# FLASH.net
KiCad netlist of a schematic drawn in Altium Designer
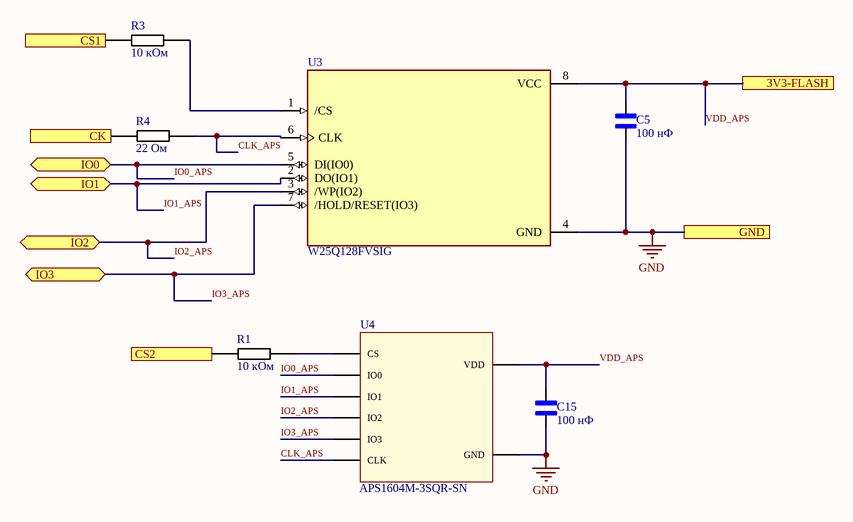
[diagram p0: FLASH.SchDoc]

(export (version "E")
  (design (tool "Eeschema 10.0.6"))
  (components
    (comp (ref "C5")
      (value "100 нФ")
      (footprint "CAPC1005X22N")
      (description "SMD Capacitor X5R(EIA) with Capacitance: 0.10uF Tol. 10%. Rated Voltage: 6.3Vdc")
      (fields (field (name "MF") "Murata") (field (name "MP") "GRM152R60J104KE19D"))
      (libsource (lib "GRM152R60J104KE19D") (part "GRM152R60J104KE19D"))
    )
    (comp (ref "C15")
      (value "100 нФ")
      (footprint "CAPC1005X22N")
      (description "SMD Capacitor X5R(EIA) with Capacitance: 0.10uF Tol. 10%. Rated Voltage: 6.3Vdc")
      (fields (field (name "MF") "Murata") (field (name "MP") "GRM152R60J104KE19D"))
      (libsource (lib "GRM152R60J104KE19D") (part "GRM152R60J104KE19D"))
    )
    (comp (ref "R1")
      (value "10 кОм")
      (footprint "Yageo RC0805JR-0710KL")
      (libsource (lib "Schlib1") (part "Yageo RC0805JR-0710KL"))
    )
    (comp (ref "R3")
      (value "10 кОм")
      (footprint "Yageo RC0805JR-0710KL")
      (libsource (lib "Schlib1") (part "Yageo RC0805JR-0710KL"))
    )
    (comp (ref "R4")
      (value "22 Ом")
      (footprint "CR0805-JW-220ELF")
      (libsource (lib "Schlib1") (part "CR0805-JW-220ELF"))
    )
    (comp (ref "U3")
      (value "W25Q128FVSIG")
      (footprint "SOIC127P790X216-8N")
      (description "FLASH - NOR Memory IC 128Mb (16M x 8) SPI - Quad I/O, QPI, DTR 133 MHz 8-SOIC")
      (fields (field (name "MF") "Winbond Electronics") (field (name "MP") "W25Q128JVSIQ"))
      (libsource (lib "W25Q128JVSIQ") (part "W25Q128JVSIQ"))
    )
    (comp (ref "U4")
      (value "APS1604M-3SQR-SN")
      (footprint "APS1604M (SOP-8)")
      (libsource (lib "Schlib1") (part "APS1604M"))
    )
  )
  (nets
    (net (code "1") (name "/CK") (class "Default")
      (node (ref "R4") (pin "1") (pinfunction "7_1") (pintype "passive"))
    )
    (net (code "2") (name "/CLK_APS") (class "Default")
      (node (ref "R4") (pin "2") (pinfunction "2_2") (pintype "passive"))
      (node (ref "U3") (pin "6") (pinfunction "CLK_6") (pintype "input"))
      (node (ref "U4") (pin "6") (pinfunction "CLK_6") (pintype "passive"))
    )
    (net (code "3") (name "/CS1") (class "Default")
      (node (ref "R3") (pin "1") (pinfunction "34_1") (pintype "passive"))
    )
    (net (code "4") (name "/CS2") (class "Default")
      (node (ref "R1") (pin "1") (pinfunction "34_1") (pintype "passive"))
    )
    (net (code "5") (name "/IO0_APS") (class "Default")
      (node (ref "U3") (pin "5") (pinfunction "DI(IO0)_5") (pintype "bidirectional"))
      (node (ref "U4") (pin "5") (pinfunction "IO0_5") (pintype "passive"))
    )
    (net (code "6") (name "/IO1_APS") (class "Default")
      (node (ref "U3") (pin "2") (pinfunction "DO(IO1)_2") (pintype "bidirectional"))
      (node (ref "U4") (pin "2") (pinfunction "IO1_2") (pintype "passive"))
    )
    (net (code "7") (name "/IO2_APS") (class "Default")
      (node (ref "U3") (pin "3") (pinfunction "/WP(IO2)_3") (pintype "bidirectional"))
      (node (ref "U4") (pin "3") (pinfunction "IO2_3") (pintype "passive"))
    )
    (net (code "8") (name "/IO3_APS") (class "Default")
      (node (ref "U3") (pin "7") (pinfunction "/HOLD/RESET(IO3)_7") (pintype "bidirectional"))
      (node (ref "U4") (pin "7") (pinfunction "IO3_7") (pintype "passive"))
    )
    (net (code "9") (name "/VDD_APS") (class "Default")
      (node (ref "C15") (pin "2") (pinfunction "2_2") (pintype "passive"))
      (node (ref "C5") (pin "2") (pinfunction "2_2") (pintype "passive"))
      (node (ref "U3") (pin "8") (pinfunction "VCC_8") (pintype "power_in"))
      (node (ref "U4") (pin "8") (pinfunction "VDD_8") (pintype "passive"))
    )
    (net (code "10") (name "GND") (class "Default")
      (node (ref "C15") (pin "1") (pinfunction "1_1") (pintype "passive"))
      (node (ref "C5") (pin "1") (pinfunction "1_1") (pintype "passive"))
      (node (ref "U3") (pin "4") (pinfunction "GND_4") (pintype "power_in"))
      (node (ref "U4") (pin "4") (pinfunction "GND_4") (pintype "passive"))
    )
    (net (code "11") (name "Net-(R1-33)") (class "Default")
      (node (ref "R1") (pin "2") (pinfunction "33_2") (pintype "passive"))
      (node (ref "U4") (pin "1") (pinfunction "CS_1") (pintype "passive"))
    )
    (net (code "12") (name "Net-(R3-33)") (class "Default")
      (node (ref "R3") (pin "2") (pinfunction "33_2") (pintype "passive"))
      (node (ref "U3") (pin "1") (pinfunction "/CS_1") (pintype "input"))
    )
  )
)
